# SCHEMATIC.net
KiCad netlist of a schematic drawn in Altium Designer
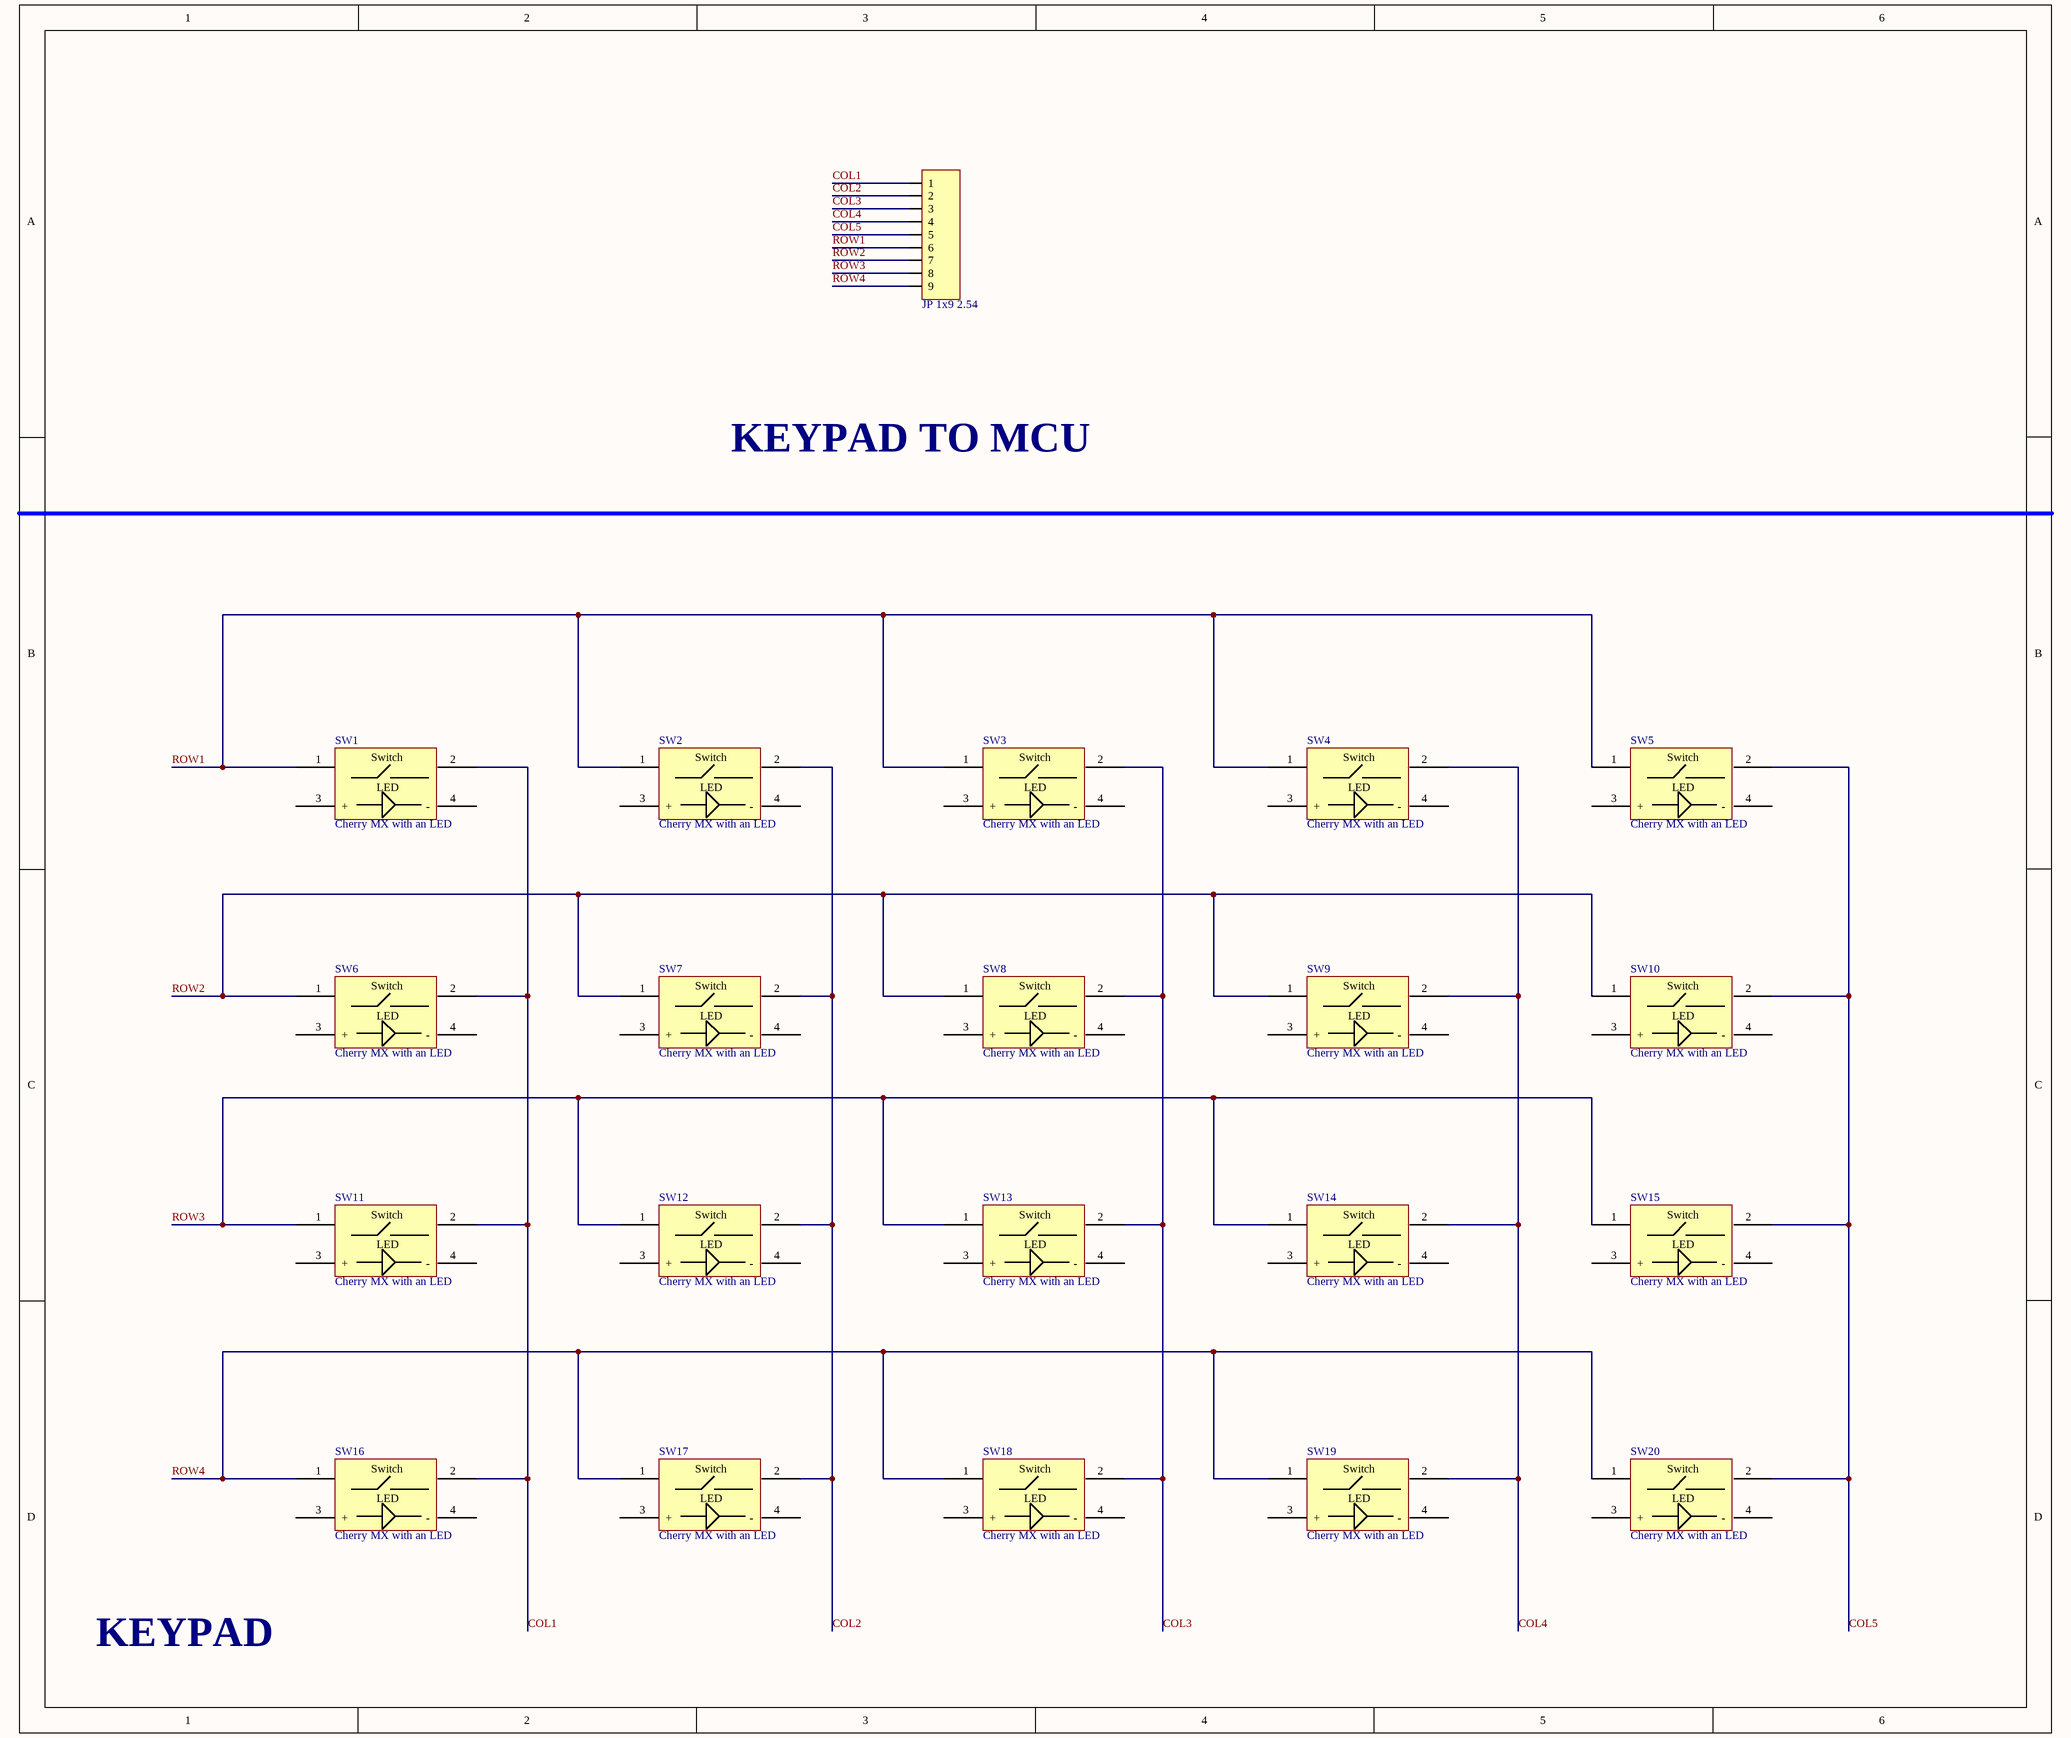
[diagram p0: SCHEMATIC.SchDoc]

(export (version "E")
  (design (tool "Eeschema 10.0.6"))
  (components
    (comp (ref "JP1")
      (value "JP 1x9 2.54")
      (footprint "JP 1x9 DC")
      (description "Cắm")
      (libsource (lib "Altium_Lib_by_KhueNguyenCreator") (part "JP 1x9 2.54 Duc Cong"))
    )
    (comp (ref "SW1")
      (value "Cherry MX with an LED")
      (footprint "MX_Cherry_LED")
      (libsource (lib "PlumPot_Library") (part "MX_Cherry_LED"))
    )
    (comp (ref "SW2")
      (value "Cherry MX with an LED")
      (footprint "MX_Cherry_LED")
      (libsource (lib "PlumPot_Library") (part "MX_Cherry_LED"))
    )
    (comp (ref "SW3")
      (value "Cherry MX with an LED")
      (footprint "MX_Cherry_LED")
      (libsource (lib "PlumPot_Library") (part "MX_Cherry_LED"))
    )
    (comp (ref "SW4")
      (value "Cherry MX with an LED")
      (footprint "MX_Cherry_LED")
      (libsource (lib "PlumPot_Library") (part "MX_Cherry_LED"))
    )
    (comp (ref "SW5")
      (value "Cherry MX with an LED")
      (footprint "MX_Cherry_LED")
      (libsource (lib "PlumPot_Library") (part "MX_Cherry_LED"))
    )
    (comp (ref "SW6")
      (value "Cherry MX with an LED")
      (footprint "MX_Cherry_LED")
      (libsource (lib "PlumPot_Library") (part "MX_Cherry_LED"))
    )
    (comp (ref "SW7")
      (value "Cherry MX with an LED")
      (footprint "MX_Cherry_LED")
      (libsource (lib "PlumPot_Library") (part "MX_Cherry_LED"))
    )
    (comp (ref "SW8")
      (value "Cherry MX with an LED")
      (footprint "MX_Cherry_LED")
      (libsource (lib "PlumPot_Library") (part "MX_Cherry_LED"))
    )
    (comp (ref "SW9")
      (value "Cherry MX with an LED")
      (footprint "MX_Cherry_LED")
      (libsource (lib "PlumPot_Library") (part "MX_Cherry_LED"))
    )
    (comp (ref "SW10")
      (value "Cherry MX with an LED")
      (footprint "MX_Cherry_LED")
      (libsource (lib "PlumPot_Library") (part "MX_Cherry_LED"))
    )
    (comp (ref "SW11")
      (value "Cherry MX with an LED")
      (footprint "MX_Cherry_LED")
      (libsource (lib "PlumPot_Library") (part "MX_Cherry_LED"))
    )
    (comp (ref "SW12")
      (value "Cherry MX with an LED")
      (footprint "MX_Cherry_LED")
      (libsource (lib "PlumPot_Library") (part "MX_Cherry_LED"))
    )
    (comp (ref "SW13")
      (value "Cherry MX with an LED")
      (footprint "MX_Cherry_LED")
      (libsource (lib "PlumPot_Library") (part "MX_Cherry_LED"))
    )
    (comp (ref "SW14")
      (value "Cherry MX with an LED")
      (footprint "MX_Cherry_LED")
      (libsource (lib "PlumPot_Library") (part "MX_Cherry_LED"))
    )
    (comp (ref "SW15")
      (value "Cherry MX with an LED")
      (footprint "MX_Cherry_LED")
      (libsource (lib "PlumPot_Library") (part "MX_Cherry_LED"))
    )
    (comp (ref "SW16")
      (value "Cherry MX with an LED")
      (footprint "MX_Cherry_LED")
      (libsource (lib "PlumPot_Library") (part "MX_Cherry_LED"))
    )
    (comp (ref "SW17")
      (value "Cherry MX with an LED")
      (footprint "MX_Cherry_LED")
      (libsource (lib "PlumPot_Library") (part "MX_Cherry_LED"))
    )
    (comp (ref "SW18")
      (value "Cherry MX with an LED")
      (footprint "MX_Cherry_LED")
      (libsource (lib "PlumPot_Library") (part "MX_Cherry_LED"))
    )
    (comp (ref "SW19")
      (value "Cherry MX with an LED")
      (footprint "MX_Cherry_LED")
      (libsource (lib "PlumPot_Library") (part "MX_Cherry_LED"))
    )
    (comp (ref "SW20")
      (value "Cherry MX with an LED")
      (footprint "MX_Cherry_LED")
      (libsource (lib "PlumPot_Library") (part "MX_Cherry_LED"))
    )
  )
  (nets
    (net (code "1") (name "/COL1") (class "Default")
      (node (ref "JP1") (pin "1") (pinfunction "1_1") (pintype "passive"))
      (node (ref "SW1") (pin "2") (pintype "passive"))
      (node (ref "SW11") (pin "2") (pintype "passive"))
      (node (ref "SW16") (pin "2") (pintype "passive"))
      (node (ref "SW6") (pin "2") (pintype "passive"))
    )
    (net (code "2") (name "/COL2") (class "Default")
      (node (ref "JP1") (pin "2") (pinfunction "2_2") (pintype "passive"))
      (node (ref "SW12") (pin "2") (pintype "passive"))
      (node (ref "SW17") (pin "2") (pintype "passive"))
      (node (ref "SW2") (pin "2") (pintype "passive"))
      (node (ref "SW7") (pin "2") (pintype "passive"))
    )
    (net (code "3") (name "/COL3") (class "Default")
      (node (ref "JP1") (pin "3") (pinfunction "3_3") (pintype "passive"))
      (node (ref "SW13") (pin "2") (pintype "passive"))
      (node (ref "SW18") (pin "2") (pintype "passive"))
      (node (ref "SW3") (pin "2") (pintype "passive"))
      (node (ref "SW8") (pin "2") (pintype "passive"))
    )
    (net (code "4") (name "/COL4") (class "Default")
      (node (ref "JP1") (pin "4") (pinfunction "4_4") (pintype "passive"))
      (node (ref "SW14") (pin "2") (pintype "passive"))
      (node (ref "SW19") (pin "2") (pintype "passive"))
      (node (ref "SW4") (pin "2") (pintype "passive"))
      (node (ref "SW9") (pin "2") (pintype "passive"))
    )
    (net (code "5") (name "/COL5") (class "Default")
      (node (ref "JP1") (pin "5") (pinfunction "5_5") (pintype "passive"))
      (node (ref "SW10") (pin "2") (pintype "passive"))
      (node (ref "SW15") (pin "2") (pintype "passive"))
      (node (ref "SW20") (pin "2") (pintype "passive"))
      (node (ref "SW5") (pin "2") (pintype "passive"))
    )
    (net (code "6") (name "/ROW1") (class "Default")
      (node (ref "JP1") (pin "6") (pinfunction "6_6") (pintype "passive"))
      (node (ref "SW1") (pin "1") (pintype "passive"))
      (node (ref "SW2") (pin "1") (pintype "passive"))
      (node (ref "SW3") (pin "1") (pintype "passive"))
      (node (ref "SW4") (pin "1") (pintype "passive"))
      (node (ref "SW5") (pin "1") (pintype "passive"))
    )
    (net (code "7") (name "/ROW2") (class "Default")
      (node (ref "JP1") (pin "7") (pinfunction "7_7") (pintype "passive"))
      (node (ref "SW10") (pin "1") (pintype "passive"))
      (node (ref "SW6") (pin "1") (pintype "passive"))
      (node (ref "SW7") (pin "1") (pintype "passive"))
      (node (ref "SW8") (pin "1") (pintype "passive"))
      (node (ref "SW9") (pin "1") (pintype "passive"))
    )
    (net (code "8") (name "/ROW3") (class "Default")
      (node (ref "JP1") (pin "8") (pinfunction "8_8") (pintype "passive"))
      (node (ref "SW11") (pin "1") (pintype "passive"))
      (node (ref "SW12") (pin "1") (pintype "passive"))
      (node (ref "SW13") (pin "1") (pintype "passive"))
      (node (ref "SW14") (pin "1") (pintype "passive"))
      (node (ref "SW15") (pin "1") (pintype "passive"))
    )
    (net (code "9") (name "/ROW4") (class "Default")
      (node (ref "JP1") (pin "9") (pinfunction "9_9") (pintype "passive"))
      (node (ref "SW16") (pin "1") (pintype "passive"))
      (node (ref "SW17") (pin "1") (pintype "passive"))
      (node (ref "SW18") (pin "1") (pintype "passive"))
      (node (ref "SW19") (pin "1") (pintype "passive"))
      (node (ref "SW20") (pin "1") (pintype "passive"))
    )
    (net (code "10") (name "unconnected-(SW1-+-Pad3)") (class "Default")
      (node (ref "SW1") (pin "3") (pinfunction "+_3") (pintype "passive"))
    )
    (net (code "11") (name "unconnected-(SW1---Pad4)") (class "Default")
      (node (ref "SW1") (pin "4") (pinfunction "-_4") (pintype "passive"))
    )
    (net (code "12") (name "unconnected-(SW2-+-Pad3)") (class "Default")
      (node (ref "SW2") (pin "3") (pinfunction "+_3") (pintype "passive"))
    )
    (net (code "13") (name "unconnected-(SW2---Pad4)") (class "Default")
      (node (ref "SW2") (pin "4") (pinfunction "-_4") (pintype "passive"))
    )
    (net (code "14") (name "unconnected-(SW3-+-Pad3)") (class "Default")
      (node (ref "SW3") (pin "3") (pinfunction "+_3") (pintype "passive"))
    )
    (net (code "15") (name "unconnected-(SW3---Pad4)") (class "Default")
      (node (ref "SW3") (pin "4") (pinfunction "-_4") (pintype "passive"))
    )
    (net (code "16") (name "unconnected-(SW4-+-Pad3)") (class "Default")
      (node (ref "SW4") (pin "3") (pinfunction "+_3") (pintype "passive"))
    )
    (net (code "17") (name "unconnected-(SW4---Pad4)") (class "Default")
      (node (ref "SW4") (pin "4") (pinfunction "-_4") (pintype "passive"))
    )
    (net (code "18") (name "unconnected-(SW5-+-Pad3)") (class "Default")
      (node (ref "SW5") (pin "3") (pinfunction "+_3") (pintype "passive"))
    )
    (net (code "19") (name "unconnected-(SW5---Pad4)") (class "Default")
      (node (ref "SW5") (pin "4") (pinfunction "-_4") (pintype "passive"))
    )
    (net (code "20") (name "unconnected-(SW6-+-Pad3)") (class "Default")
      (node (ref "SW6") (pin "3") (pinfunction "+_3") (pintype "passive"))
    )
    (net (code "21") (name "unconnected-(SW6---Pad4)") (class "Default")
      (node (ref "SW6") (pin "4") (pinfunction "-_4") (pintype "passive"))
    )
    (net (code "22") (name "unconnected-(SW7-+-Pad3)") (class "Default")
      (node (ref "SW7") (pin "3") (pinfunction "+_3") (pintype "passive"))
    )
    (net (code "23") (name "unconnected-(SW7---Pad4)") (class "Default")
      (node (ref "SW7") (pin "4") (pinfunction "-_4") (pintype "passive"))
    )
    (net (code "24") (name "unconnected-(SW8-+-Pad3)") (class "Default")
      (node (ref "SW8") (pin "3") (pinfunction "+_3") (pintype "passive"))
    )
    (net (code "25") (name "unconnected-(SW8---Pad4)") (class "Default")
      (node (ref "SW8") (pin "4") (pinfunction "-_4") (pintype "passive"))
    )
    (net (code "26") (name "unconnected-(SW9-+-Pad3)") (class "Default")
      (node (ref "SW9") (pin "3") (pinfunction "+_3") (pintype "passive"))
    )
    (net (code "27") (name "unconnected-(SW9---Pad4)") (class "Default")
      (node (ref "SW9") (pin "4") (pinfunction "-_4") (pintype "passive"))
    )
    (net (code "28") (name "unconnected-(SW10-+-Pad3)") (class "Default")
      (node (ref "SW10") (pin "3") (pinfunction "+_3") (pintype "passive"))
    )
    (net (code "29") (name "unconnected-(SW10---Pad4)") (class "Default")
      (node (ref "SW10") (pin "4") (pinfunction "-_4") (pintype "passive"))
    )
    (net (code "30") (name "unconnected-(SW11-+-Pad3)") (class "Default")
      (node (ref "SW11") (pin "3") (pinfunction "+_3") (pintype "passive"))
    )
    (net (code "31") (name "unconnected-(SW11---Pad4)") (class "Default")
      (node (ref "SW11") (pin "4") (pinfunction "-_4") (pintype "passive"))
    )
    (net (code "32") (name "unconnected-(SW12-+-Pad3)") (class "Default")
      (node (ref "SW12") (pin "3") (pinfunction "+_3") (pintype "passive"))
    )
    (net (code "33") (name "unconnected-(SW12---Pad4)") (class "Default")
      (node (ref "SW12") (pin "4") (pinfunction "-_4") (pintype "passive"))
    )
    (net (code "34") (name "unconnected-(SW13-+-Pad3)") (class "Default")
      (node (ref "SW13") (pin "3") (pinfunction "+_3") (pintype "passive"))
    )
    (net (code "35") (name "unconnected-(SW13---Pad4)") (class "Default")
      (node (ref "SW13") (pin "4") (pinfunction "-_4") (pintype "passive"))
    )
    (net (code "36") (name "unconnected-(SW14-+-Pad3)") (class "Default")
      (node (ref "SW14") (pin "3") (pinfunction "+_3") (pintype "passive"))
    )
    (net (code "37") (name "unconnected-(SW14---Pad4)") (class "Default")
      (node (ref "SW14") (pin "4") (pinfunction "-_4") (pintype "passive"))
    )
    (net (code "38") (name "unconnected-(SW15-+-Pad3)") (class "Default")
      (node (ref "SW15") (pin "3") (pinfunction "+_3") (pintype "passive"))
    )
    (net (code "39") (name "unconnected-(SW15---Pad4)") (class "Default")
      (node (ref "SW15") (pin "4") (pinfunction "-_4") (pintype "passive"))
    )
    (net (code "40") (name "unconnected-(SW16-+-Pad3)") (class "Default")
      (node (ref "SW16") (pin "3") (pinfunction "+_3") (pintype "passive"))
    )
    (net (code "41") (name "unconnected-(SW16---Pad4)") (class "Default")
      (node (ref "SW16") (pin "4") (pinfunction "-_4") (pintype "passive"))
    )
    (net (code "42") (name "unconnected-(SW17-+-Pad3)") (class "Default")
      (node (ref "SW17") (pin "3") (pinfunction "+_3") (pintype "passive"))
    )
    (net (code "43") (name "unconnected-(SW17---Pad4)") (class "Default")
      (node (ref "SW17") (pin "4") (pinfunction "-_4") (pintype "passive"))
    )
    (net (code "44") (name "unconnected-(SW18-+-Pad3)") (class "Default")
      (node (ref "SW18") (pin "3") (pinfunction "+_3") (pintype "passive"))
    )
    (net (code "45") (name "unconnected-(SW18---Pad4)") (class "Default")
      (node (ref "SW18") (pin "4") (pinfunction "-_4") (pintype "passive"))
    )
    (net (code "46") (name "unconnected-(SW19-+-Pad3)") (class "Default")
      (node (ref "SW19") (pin "3") (pinfunction "+_3") (pintype "passive"))
    )
    (net (code "47") (name "unconnected-(SW19---Pad4)") (class "Default")
      (node (ref "SW19") (pin "4") (pinfunction "-_4") (pintype "passive"))
    )
    (net (code "48") (name "unconnected-(SW20-+-Pad3)") (class "Default")
      (node (ref "SW20") (pin "3") (pinfunction "+_3") (pintype "passive"))
    )
    (net (code "49") (name "unconnected-(SW20---Pad4)") (class "Default")
      (node (ref "SW20") (pin "4") (pinfunction "-_4") (pintype "passive"))
    )
  )
)
